# ROM24k_final_rev01.net
KiCad netlist of a schematic drawn in EAGLE
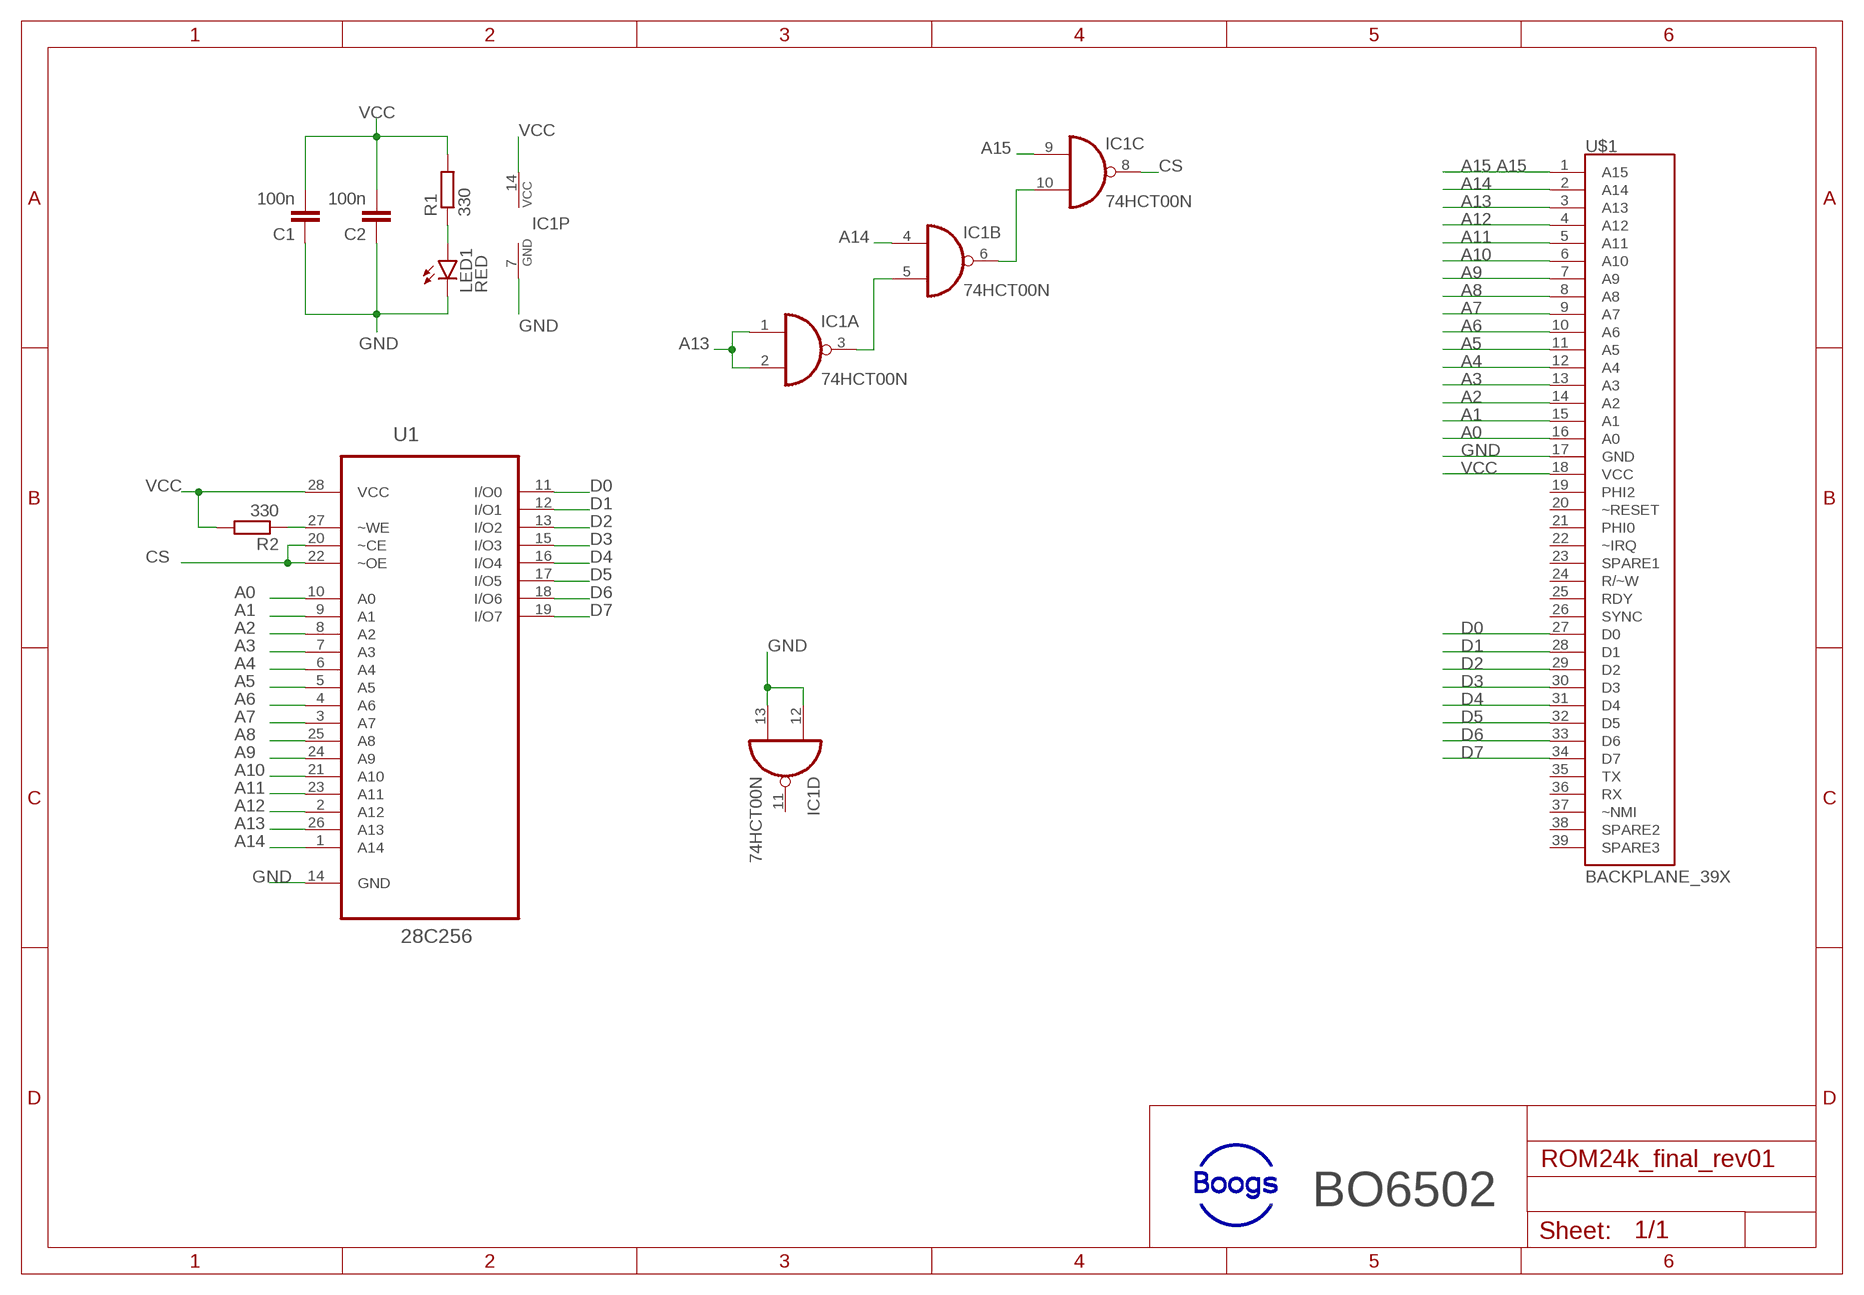
[diagram p0: schematic, sheet 1]

(export (version "E")
  (design (tool "Eeschema 10.0.6"))
  (components
    (comp (ref "C1")
      (value "100n")
      (footprint "eagle-import:C025-025X050")
      (libsource (lib "eagle-import") (part "C-EU025-025X050"))
    )
    (comp (ref "C2")
      (value "100n")
      (footprint "eagle-import:C025-025X050")
      (libsource (lib "eagle-import") (part "C-EU025-025X050"))
    )
    (comp (ref "IC1")
      (value "74HCT00N")
      (footprint "eagle-import:DIL14")
      (libsource (lib "eagle-import") (part "7400NHCT"))
    )
    (comp (ref "LED1")
      (value "RED")
      (footprint "eagle-import:LED5MM")
      (libsource (lib "eagle-import") (part "LED5MM"))
    )
    (comp (ref "R1")
      (value "330")
      (footprint "eagle-import:0207_10")
      (libsource (lib "eagle-import") (part "R-EU_0207/10"))
    )
    (comp (ref "R2")
      (value "330")
      (footprint "eagle-import:0207_10")
      (libsource (lib "eagle-import") (part "R-EU_0207/10"))
    )
    (comp (ref "U$1")
      (value "BACKPLANE_39X")
      (footprint "eagle-import:BP_39X")
      (fields (field (name "A15") "A15"))
      (libsource (lib "eagle-import") (part "BACKPLANE_39X"))
    )
    (comp (ref "U1")
      (value "28C256")
      (footprint "eagle-import:DIP254P1524X482-28")
      (fields (field (name "MF") "Microchip") (field (name "MP") "AT28C256-15PU"))
      (libsource (lib "eagle-import") (part "AT28C256-15PU"))
    )
  )
  (nets
    (net (code "1") (name "/A0") (class "Default")
      (node (ref "U$1") (pin "16") (pinfunction "A0_16") (pintype "bidirectional"))
      (node (ref "U1") (pin "10") (pinfunction "A0_10") (pintype "input"))
    )
    (net (code "2") (name "/A1") (class "Default")
      (node (ref "U$1") (pin "15") (pinfunction "A1_15") (pintype "bidirectional"))
      (node (ref "U1") (pin "9") (pinfunction "A1_9") (pintype "input"))
    )
    (net (code "3") (name "/A2") (class "Default")
      (node (ref "U$1") (pin "14") (pinfunction "A2_14") (pintype "bidirectional"))
      (node (ref "U1") (pin "8") (pinfunction "A2_8") (pintype "input"))
    )
    (net (code "4") (name "/A3") (class "Default")
      (node (ref "U$1") (pin "13") (pinfunction "A3_13") (pintype "bidirectional"))
      (node (ref "U1") (pin "7") (pinfunction "A3_7") (pintype "input"))
    )
    (net (code "5") (name "/A4") (class "Default")
      (node (ref "U$1") (pin "12") (pinfunction "A4_12") (pintype "bidirectional"))
      (node (ref "U1") (pin "6") (pinfunction "A4_6") (pintype "input"))
    )
    (net (code "6") (name "/A5") (class "Default")
      (node (ref "U$1") (pin "11") (pinfunction "A5_11") (pintype "bidirectional"))
      (node (ref "U1") (pin "5") (pinfunction "A5_5") (pintype "input"))
    )
    (net (code "7") (name "/A6") (class "Default")
      (node (ref "U$1") (pin "10") (pinfunction "A6_10") (pintype "bidirectional"))
      (node (ref "U1") (pin "4") (pinfunction "A6_4") (pintype "input"))
    )
    (net (code "8") (name "/A7") (class "Default")
      (node (ref "U$1") (pin "9") (pinfunction "A7_9") (pintype "bidirectional"))
      (node (ref "U1") (pin "3") (pinfunction "A7_3") (pintype "input"))
    )
    (net (code "9") (name "/A8") (class "Default")
      (node (ref "U$1") (pin "8") (pinfunction "A8_8") (pintype "bidirectional"))
      (node (ref "U1") (pin "25") (pinfunction "A8_25") (pintype "input"))
    )
    (net (code "10") (name "/A9") (class "Default")
      (node (ref "U$1") (pin "7") (pinfunction "A9_7") (pintype "bidirectional"))
      (node (ref "U1") (pin "24") (pinfunction "A9_24") (pintype "input"))
    )
    (net (code "11") (name "/A10") (class "Default")
      (node (ref "U$1") (pin "6") (pinfunction "A10_6") (pintype "bidirectional"))
      (node (ref "U1") (pin "21") (pinfunction "A10_21") (pintype "input"))
    )
    (net (code "12") (name "/A11") (class "Default")
      (node (ref "U$1") (pin "5") (pinfunction "A11_5") (pintype "bidirectional"))
      (node (ref "U1") (pin "23") (pinfunction "A11_23") (pintype "input"))
    )
    (net (code "13") (name "/A12") (class "Default")
      (node (ref "U$1") (pin "4") (pinfunction "A12_4") (pintype "bidirectional"))
      (node (ref "U1") (pin "2") (pinfunction "A12_2") (pintype "input"))
    )
    (net (code "14") (name "/A13") (class "Default")
      (node (ref "IC1") (pin "1") (pinfunction "I0_1") (pintype "input"))
      (node (ref "IC1") (pin "2") (pinfunction "I1_2") (pintype "input"))
      (node (ref "U$1") (pin "3") (pinfunction "A13_3") (pintype "bidirectional"))
      (node (ref "U1") (pin "26") (pinfunction "A13_26") (pintype "input"))
    )
    (net (code "15") (name "/A14") (class "Default")
      (node (ref "IC1") (pin "4") (pinfunction "I0_4") (pintype "input"))
      (node (ref "U$1") (pin "2") (pinfunction "A14_2") (pintype "bidirectional"))
      (node (ref "U1") (pin "1") (pinfunction "A14_1") (pintype "input"))
    )
    (net (code "16") (name "/A15") (class "Default")
      (node (ref "IC1") (pin "9") (pinfunction "I0_9") (pintype "input"))
      (node (ref "U$1") (pin "1") (pinfunction "A15_1") (pintype "bidirectional"))
    )
    (net (code "17") (name "/CS") (class "Default")
      (node (ref "IC1") (pin "8") (pinfunction "O_8") (pintype "output"))
      (node (ref "U1") (pin "20") (pinfunction "~{CE}_20") (pintype "input"))
      (node (ref "U1") (pin "22") (pinfunction "~{OE}_22") (pintype "input"))
    )
    (net (code "18") (name "/D0") (class "Default")
      (node (ref "U$1") (pin "27") (pinfunction "D0_27") (pintype "bidirectional"))
      (node (ref "U1") (pin "11") (pinfunction "I/O0_11") (pintype "bidirectional"))
    )
    (net (code "19") (name "/D1") (class "Default")
      (node (ref "U$1") (pin "28") (pinfunction "D1_28") (pintype "bidirectional"))
      (node (ref "U1") (pin "12") (pinfunction "I/O1_12") (pintype "bidirectional"))
    )
    (net (code "20") (name "/D2") (class "Default")
      (node (ref "U$1") (pin "29") (pinfunction "D2_29") (pintype "bidirectional"))
      (node (ref "U1") (pin "13") (pinfunction "I/O2_13") (pintype "bidirectional"))
    )
    (net (code "21") (name "/D3") (class "Default")
      (node (ref "U$1") (pin "30") (pinfunction "D3_30") (pintype "bidirectional"))
      (node (ref "U1") (pin "15") (pinfunction "I/O3_15") (pintype "bidirectional"))
    )
    (net (code "22") (name "/D4") (class "Default")
      (node (ref "U$1") (pin "31") (pinfunction "D4_31") (pintype "bidirectional"))
      (node (ref "U1") (pin "16") (pinfunction "I/O4_16") (pintype "bidirectional"))
    )
    (net (code "23") (name "/D5") (class "Default")
      (node (ref "U$1") (pin "32") (pinfunction "D5_32") (pintype "bidirectional"))
      (node (ref "U1") (pin "17") (pinfunction "I/O5_17") (pintype "bidirectional"))
    )
    (net (code "24") (name "/D6") (class "Default")
      (node (ref "U$1") (pin "33") (pinfunction "D6_33") (pintype "bidirectional"))
      (node (ref "U1") (pin "18") (pinfunction "I/O6_18") (pintype "bidirectional"))
    )
    (net (code "25") (name "/D7") (class "Default")
      (node (ref "U$1") (pin "34") (pinfunction "D7_34") (pintype "bidirectional"))
      (node (ref "U1") (pin "19") (pinfunction "I/O7_19") (pintype "bidirectional"))
    )
    (net (code "26") (name "/GND") (class "Default")
      (node (ref "C1") (pin "1") (pinfunction "1_1") (pintype "passive"))
      (node (ref "C2") (pin "1") (pinfunction "1_1") (pintype "passive"))
      (node (ref "IC1") (pin "12") (pinfunction "I0_12") (pintype "input"))
      (node (ref "IC1") (pin "13") (pinfunction "I1_13") (pintype "input"))
      (node (ref "IC1") (pin "7") (pinfunction "GND_7") (pintype "power_in"))
      (node (ref "LED1") (pin "K") (pinfunction "C_K") (pintype "passive"))
      (node (ref "U$1") (pin "17") (pinfunction "GND_17") (pintype "bidirectional"))
      (node (ref "U1") (pin "14") (pinfunction "GND_14") (pintype "passive"))
    )
    (net (code "27") (name "/VCC") (class "Default")
      (node (ref "C1") (pin "2") (pinfunction "2_2") (pintype "passive"))
      (node (ref "C2") (pin "2") (pinfunction "2_2") (pintype "passive"))
      (node (ref "IC1") (pin "14") (pinfunction "VCC_14") (pintype "power_in"))
      (node (ref "R1") (pin "2") (pinfunction "2_2") (pintype "passive"))
      (node (ref "R2") (pin "2") (pinfunction "2_2") (pintype "passive"))
      (node (ref "U$1") (pin "18") (pinfunction "VCC_18") (pintype "bidirectional"))
      (node (ref "U1") (pin "28") (pinfunction "VCC_28") (pintype "power_in"))
    )
    (net (code "28") (name "Net-(IC1A-O)") (class "Default")
      (node (ref "IC1") (pin "3") (pinfunction "O_3") (pintype "output"))
      (node (ref "IC1") (pin "5") (pinfunction "I1_5") (pintype "input"))
    )
    (net (code "29") (name "Net-(IC1B-O)") (class "Default")
      (node (ref "IC1") (pin "10") (pinfunction "I1_10") (pintype "input"))
      (node (ref "IC1") (pin "6") (pinfunction "O_6") (pintype "output"))
    )
    (net (code "30") (name "Net-(LED1-PadA)") (class "Default")
      (node (ref "LED1") (pin "A") (pinfunction "A_A") (pintype "passive"))
      (node (ref "R1") (pin "1") (pinfunction "1_1") (pintype "passive"))
    )
    (net (code "31") (name "Net-(U1-~{WE})") (class "Default")
      (node (ref "R2") (pin "1") (pinfunction "1_1") (pintype "passive"))
      (node (ref "U1") (pin "27") (pinfunction "~{WE}_27") (pintype "input"))
    )
    (net (code "32") (name "unconnected-(IC1D-O-Pad11)") (class "Default")
      (node (ref "IC1") (pin "11") (pinfunction "O_11") (pintype "output"))
    )
    (net (code "33") (name "unconnected-(U$1-PHI0-Pad21)") (class "Default")
      (node (ref "U$1") (pin "21") (pinfunction "PHI0_21") (pintype "bidirectional"))
    )
    (net (code "34") (name "unconnected-(U$1-PHI2-Pad19)") (class "Default")
      (node (ref "U$1") (pin "19") (pinfunction "PHI2_19") (pintype "bidirectional"))
    )
    (net (code "35") (name "unconnected-(U$1-RDY-Pad25)") (class "Default")
      (node (ref "U$1") (pin "25") (pinfunction "RDY_25") (pintype "bidirectional"))
    )
    (net (code "36") (name "unconnected-(U$1-RX-Pad36)") (class "Default")
      (node (ref "U$1") (pin "36") (pinfunction "RX_36") (pintype "bidirectional"))
    )
    (net (code "37") (name "unconnected-(U$1-R{slash}~{W}-Pad24)") (class "Default")
      (node (ref "U$1") (pin "24") (pinfunction "R/~{W}_24") (pintype "bidirectional"))
    )
    (net (code "38") (name "unconnected-(U$1-SPARE1-Pad23)") (class "Default")
      (node (ref "U$1") (pin "23") (pinfunction "SPARE1_23") (pintype "bidirectional"))
    )
    (net (code "39") (name "unconnected-(U$1-SPARE2-Pad38)") (class "Default")
      (node (ref "U$1") (pin "38") (pinfunction "SPARE2_38") (pintype "bidirectional"))
    )
    (net (code "40") (name "unconnected-(U$1-SPARE3-Pad39)") (class "Default")
      (node (ref "U$1") (pin "39") (pinfunction "SPARE3_39") (pintype "bidirectional"))
    )
    (net (code "41") (name "unconnected-(U$1-SYNC-Pad26)") (class "Default")
      (node (ref "U$1") (pin "26") (pinfunction "SYNC_26") (pintype "bidirectional"))
    )
    (net (code "42") (name "unconnected-(U$1-TX-Pad35)") (class "Default")
      (node (ref "U$1") (pin "35") (pinfunction "TX_35") (pintype "bidirectional"))
    )
    (net (code "43") (name "unconnected-(U$1-~{IRQ}-Pad22)") (class "Default")
      (node (ref "U$1") (pin "22") (pinfunction "~{IRQ}_22") (pintype "bidirectional"))
    )
    (net (code "44") (name "unconnected-(U$1-~{NMI}-Pad37)") (class "Default")
      (node (ref "U$1") (pin "37") (pinfunction "~{NMI}_37") (pintype "bidirectional"))
    )
    (net (code "45") (name "unconnected-(U$1-~{RESET}-Pad20)") (class "Default")
      (node (ref "U$1") (pin "20") (pinfunction "~{RESET}_20") (pintype "bidirectional"))
    )
  )
)
